# ENERGIS_FPC-1_0_0.net
KiCad netlist of a schematic drawn in EAGLE
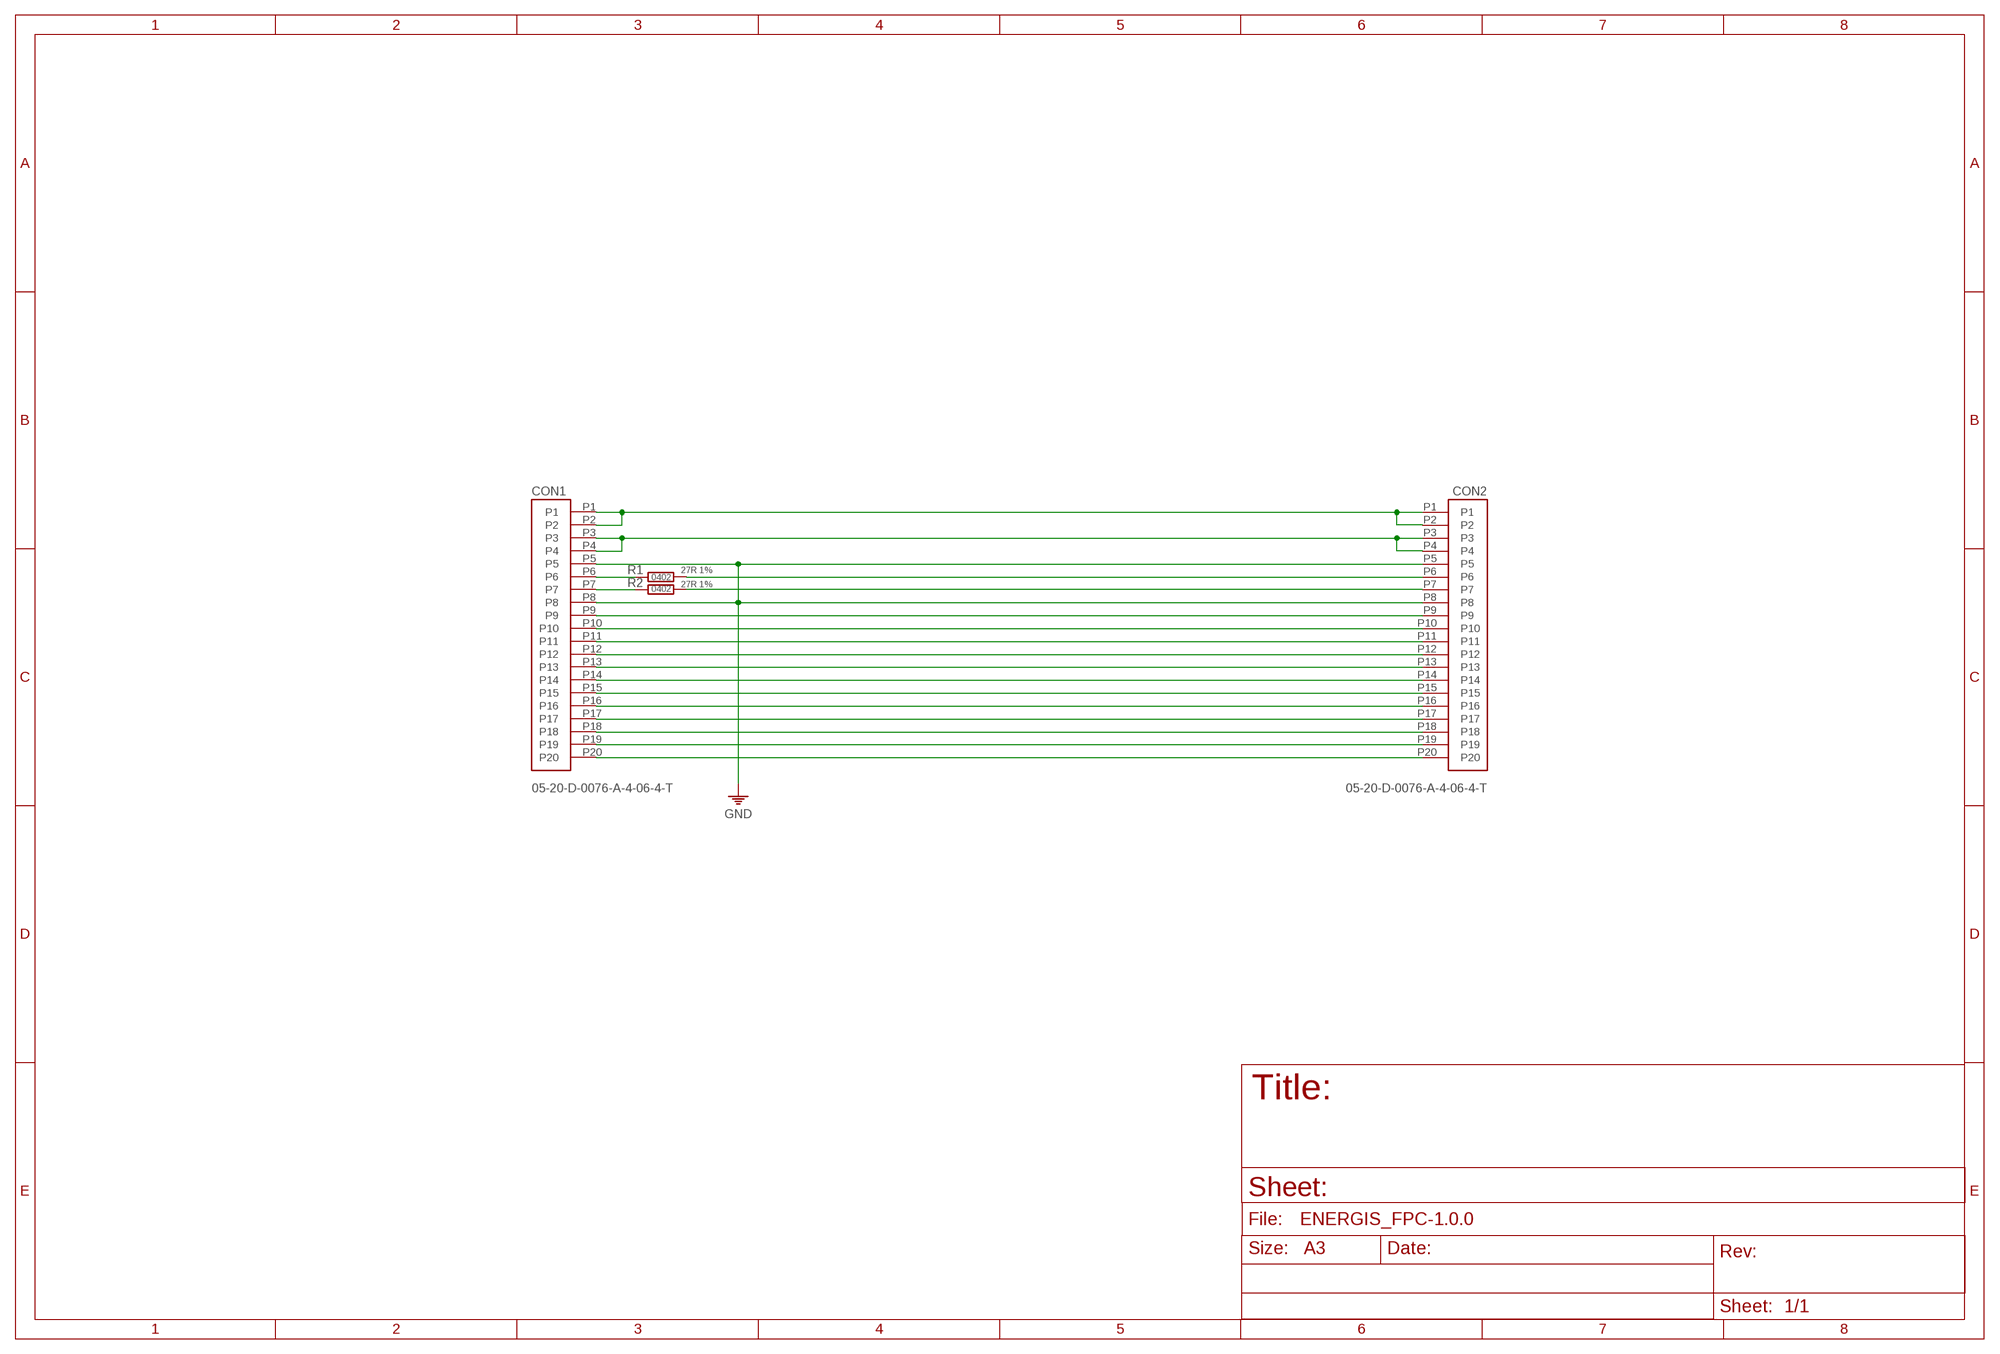
[diagram p0: schematic, sheet 1]

(export (version "E")
  (design (tool "Eeschema 10.0.6"))
  (components
    (comp (ref "CON1")
      (value "05-20-D-0076-A-4-06-4-T")
      (footprint "eagle-import:05-20-D-0076-A-4-06-4-T")
      (libsource (lib "eagle-import") (part "05-20-D-0076-A-4-06-4-T"))
    )
    (comp (ref "CON2")
      (value "05-20-D-0076-A-4-06-4-T")
      (footprint "eagle-import:05-20-D-0076-A-4-06-4-T")
      (libsource (lib "eagle-import") (part "05-20-D-0076-A-4-06-4-T"))
    )
    (comp (ref "R1")
      (value "27R 1%")
      (footprint "eagle-import:0402")
      (fields (field (name "PACKAGE") "0402") (field (name "LCSC_PART") "C138021"))
      (libsource (lib "eagle-import") (part "27R-1%0402"))
    )
    (comp (ref "R2")
      (value "27R 1%")
      (footprint "eagle-import:0402")
      (fields (field (name "PACKAGE") "0402") (field (name "LCSC_PART") "C138021"))
      (libsource (lib "eagle-import") (part "27R-1%0402"))
    )
  )
  (nets
    (net (code "1") (name "GND") (class "Default")
      (node (ref "CON1") (pin "P5") (pinfunction "P5_P5") (pintype "bidirectional"))
      (node (ref "CON1") (pin "P8") (pinfunction "P8_P8") (pintype "bidirectional"))
      (node (ref "CON2") (pin "P5") (pinfunction "P5_P5") (pintype "bidirectional"))
      (node (ref "CON2") (pin "P8") (pinfunction "P8_P8") (pintype "bidirectional"))
    )
    (net (code "2") (name "Net-(CON1-PadP1)") (class "Default")
      (node (ref "CON1") (pin "P1") (pinfunction "P1_P1") (pintype "bidirectional"))
      (node (ref "CON1") (pin "P2") (pinfunction "P2_P2") (pintype "bidirectional"))
      (node (ref "CON2") (pin "P1") (pinfunction "P1_P1") (pintype "bidirectional"))
      (node (ref "CON2") (pin "P2") (pinfunction "P2_P2") (pintype "bidirectional"))
    )
    (net (code "3") (name "Net-(CON1-PadP3)") (class "Default")
      (node (ref "CON1") (pin "P3") (pinfunction "P3_P3") (pintype "bidirectional"))
      (node (ref "CON1") (pin "P4") (pinfunction "P4_P4") (pintype "bidirectional"))
      (node (ref "CON2") (pin "P3") (pinfunction "P3_P3") (pintype "bidirectional"))
      (node (ref "CON2") (pin "P4") (pinfunction "P4_P4") (pintype "bidirectional"))
    )
    (net (code "4") (name "Net-(CON1-PadP6)") (class "Default")
      (node (ref "CON1") (pin "P6") (pinfunction "P6_P6") (pintype "bidirectional"))
      (node (ref "R1") (pin "1") (pinfunction "1_1") (pintype "passive"))
    )
    (net (code "5") (name "Net-(CON1-PadP7)") (class "Default")
      (node (ref "CON1") (pin "P7") (pinfunction "P7_P7") (pintype "bidirectional"))
      (node (ref "R2") (pin "1") (pinfunction "1_1") (pintype "passive"))
    )
    (net (code "6") (name "Net-(CON1-PadP9)") (class "Default")
      (node (ref "CON1") (pin "P9") (pinfunction "P9_P9") (pintype "bidirectional"))
      (node (ref "CON2") (pin "P9") (pinfunction "P9_P9") (pintype "bidirectional"))
    )
    (net (code "7") (name "Net-(CON1-PadP10)") (class "Default")
      (node (ref "CON1") (pin "P10") (pinfunction "P10_P10") (pintype "bidirectional"))
      (node (ref "CON2") (pin "P10") (pinfunction "P10_P10") (pintype "bidirectional"))
    )
    (net (code "8") (name "Net-(CON1-PadP11)") (class "Default")
      (node (ref "CON1") (pin "P11") (pinfunction "P11_P11") (pintype "bidirectional"))
      (node (ref "CON2") (pin "P11") (pinfunction "P11_P11") (pintype "bidirectional"))
    )
    (net (code "9") (name "Net-(CON1-PadP12)") (class "Default")
      (node (ref "CON1") (pin "P12") (pinfunction "P12_P12") (pintype "bidirectional"))
      (node (ref "CON2") (pin "P12") (pinfunction "P12_P12") (pintype "bidirectional"))
    )
    (net (code "10") (name "Net-(CON1-PadP13)") (class "Default")
      (node (ref "CON1") (pin "P13") (pinfunction "P13_P13") (pintype "bidirectional"))
      (node (ref "CON2") (pin "P13") (pinfunction "P13_P13") (pintype "bidirectional"))
    )
    (net (code "11") (name "Net-(CON1-PadP14)") (class "Default")
      (node (ref "CON1") (pin "P14") (pinfunction "P14_P14") (pintype "bidirectional"))
      (node (ref "CON2") (pin "P14") (pinfunction "P14_P14") (pintype "bidirectional"))
    )
    (net (code "12") (name "Net-(CON1-PadP15)") (class "Default")
      (node (ref "CON1") (pin "P15") (pinfunction "P15_P15") (pintype "bidirectional"))
      (node (ref "CON2") (pin "P15") (pinfunction "P15_P15") (pintype "bidirectional"))
    )
    (net (code "13") (name "Net-(CON1-PadP16)") (class "Default")
      (node (ref "CON1") (pin "P16") (pinfunction "P16_P16") (pintype "bidirectional"))
      (node (ref "CON2") (pin "P16") (pinfunction "P16_P16") (pintype "bidirectional"))
    )
    (net (code "14") (name "Net-(CON1-PadP17)") (class "Default")
      (node (ref "CON1") (pin "P17") (pinfunction "P17_P17") (pintype "bidirectional"))
      (node (ref "CON2") (pin "P17") (pinfunction "P17_P17") (pintype "bidirectional"))
    )
    (net (code "15") (name "Net-(CON1-PadP18)") (class "Default")
      (node (ref "CON1") (pin "P18") (pinfunction "P18_P18") (pintype "bidirectional"))
      (node (ref "CON2") (pin "P18") (pinfunction "P18_P18") (pintype "bidirectional"))
    )
    (net (code "16") (name "Net-(CON1-PadP19)") (class "Default")
      (node (ref "CON1") (pin "P19") (pinfunction "P19_P19") (pintype "bidirectional"))
      (node (ref "CON2") (pin "P19") (pinfunction "P19_P19") (pintype "bidirectional"))
    )
    (net (code "17") (name "Net-(CON1-PadP20)") (class "Default")
      (node (ref "CON1") (pin "P20") (pinfunction "P20_P20") (pintype "bidirectional"))
      (node (ref "CON2") (pin "P20") (pinfunction "P20_P20") (pintype "bidirectional"))
    )
    (net (code "18") (name "Net-(CON2-PadP6)") (class "Default")
      (node (ref "CON2") (pin "P6") (pinfunction "P6_P6") (pintype "bidirectional"))
      (node (ref "R1") (pin "2") (pinfunction "2_2") (pintype "passive"))
    )
    (net (code "19") (name "Net-(CON2-PadP7)") (class "Default")
      (node (ref "CON2") (pin "P7") (pinfunction "P7_P7") (pintype "bidirectional"))
      (node (ref "R2") (pin "2") (pinfunction "2_2") (pintype "passive"))
    )
  )
)
